# RF.net
KiCad netlist of a schematic drawn in Altium Designer
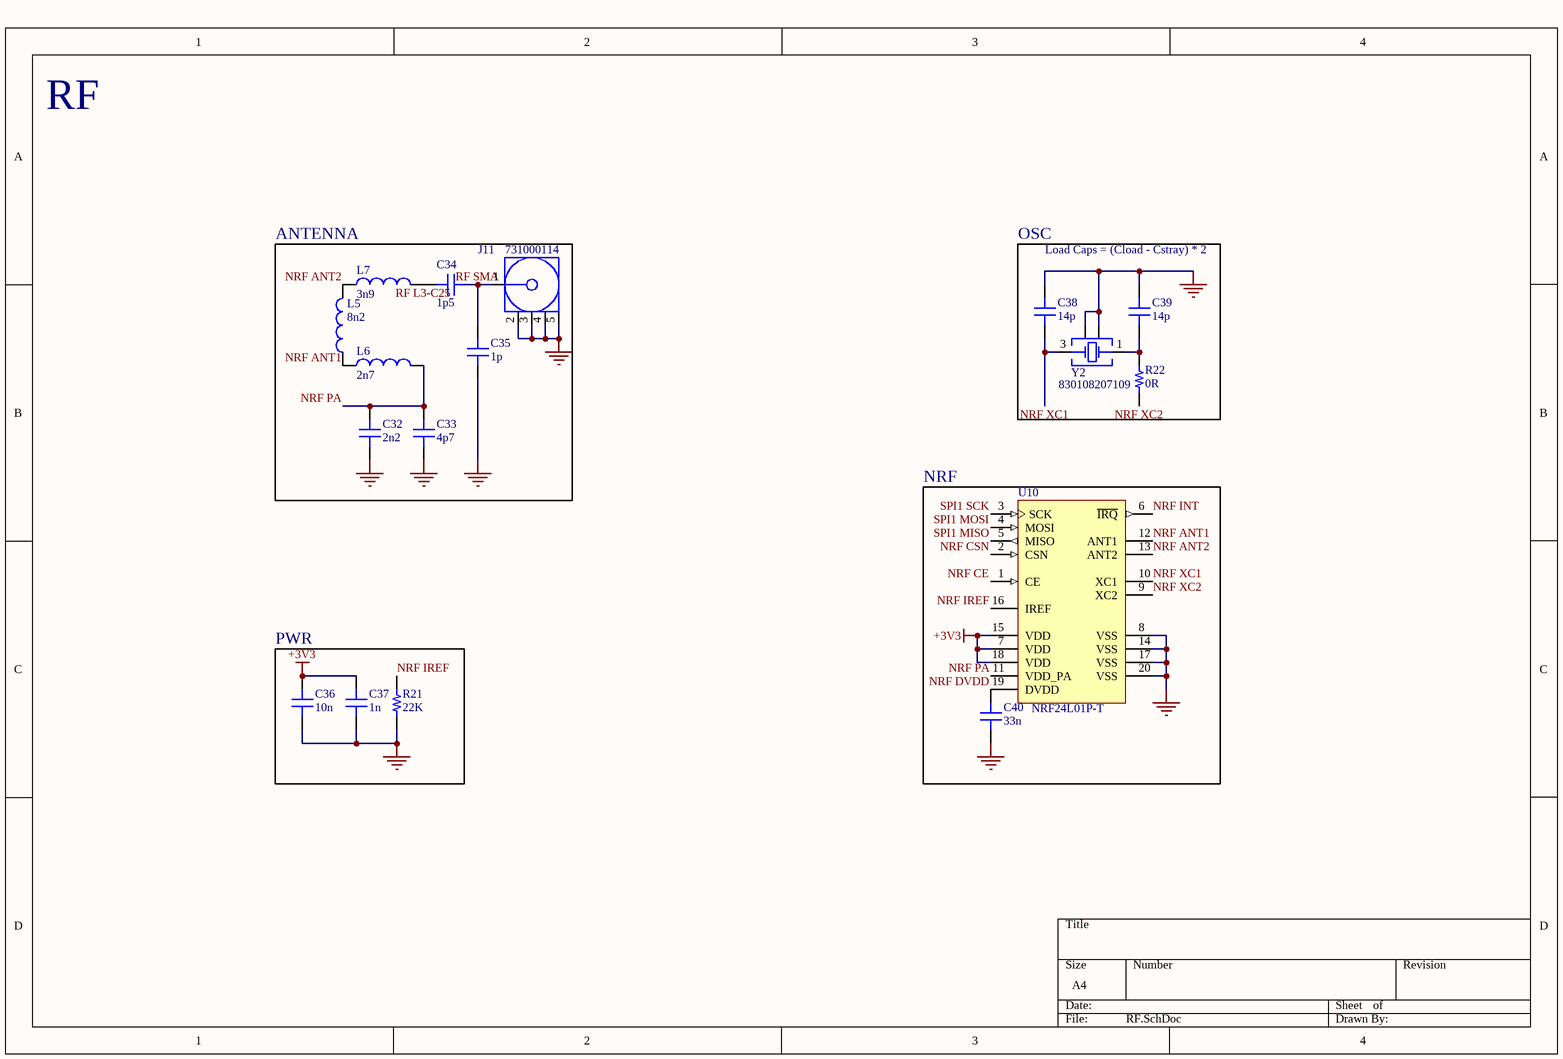
[diagram p0: RF.SchDoc]

(export (version "E")
  (design (tool "Eeschema 10.0.6"))
  (components
    (comp (ref "C32")
      (value "2n2")
      (footprint "CAP 0402_1005")
      (description "CAP CER 0402 10NF 16V X7R 10%")
      (fields (field (name "PART NUMBER") "C0402C103K4REC7867") (field (name "MANUFACTURER") "KEMET"))
      (libsource (lib "Celestial Altium Library - altium_library") (part "Capacitor"))
    )
    (comp (ref "C33")
      (value "4p7")
      (footprint "CAP 0402_1005")
      (description "CAP CER 0402 10NF 16V X7R 10%")
      (fields (field (name "PART NUMBER") "C0402C103K4REC7867") (field (name "MANUFACTURER") "KEMET"))
      (libsource (lib "Celestial Altium Library - altium_library") (part "Capacitor"))
    )
    (comp (ref "C34")
      (value "1p5")
      (footprint "CAP 0402_1005")
      (description "CAP CER 0402 10NF 16V X7R 10%")
      (fields (field (name "PART NUMBER") "C0402C103K4REC7867") (field (name "MANUFACTURER") "KEMET"))
      (libsource (lib "Celestial Altium Library - altium_library") (part "Capacitor"))
    )
    (comp (ref "C35")
      (value "1p")
      (footprint "CAP 0402_1005")
      (description "CAP CER 0402 10NF 16V X7R 10%")
      (fields (field (name "PART NUMBER") "C0402C103K4REC7867") (field (name "MANUFACTURER") "KEMET"))
      (libsource (lib "Celestial Altium Library - altium_library") (part "Capacitor"))
    )
    (comp (ref "C36")
      (value "10n")
      (footprint "CAP 0402_1005")
      (description "CAP CER 0402 10NF 16V X7R 10%")
      (fields (field (name "PART NUMBER") "C0402C103K4REC7867") (field (name "MANUFACTURER") "KEMET"))
      (libsource (lib "Celestial Altium Library - altium_library") (part "Capacitor"))
    )
    (comp (ref "C37")
      (value "1n")
      (footprint "CAP 0402_1005")
      (description "CAP CER 0402 10NF 16V X7R 10%")
      (fields (field (name "PART NUMBER") "C0402C103K4REC7867") (field (name "MANUFACTURER") "KEMET"))
      (libsource (lib "Celestial Altium Library - altium_library") (part "Capacitor"))
    )
    (comp (ref "C38")
      (value "14p")
      (footprint "CAP 0402_1005")
      (description "CAP CER 14PF 50V C0G/NP0 0402")
      (fields (field (name "PART NUMBER") "GJM1555C1H140GB01D"))
      (libsource (lib "Celestial Altium Library - altium_library") (part "Capacitor"))
    )
    (comp (ref "C39")
      (value "14p")
      (footprint "CAP 0402_1005")
      (description "CAP CER 14PF 50V C0G/NP0 0402")
      (fields (field (name "PART NUMBER") "GJM1555C1H140GB01D"))
      (libsource (lib "Celestial Altium Library - altium_library") (part "Capacitor"))
    )
    (comp (ref "C40")
      (value "33n")
      (footprint "CAP 0402_1005")
      (description "CAP CER 33PF 16V X7R 0402")
      (fields (field (name "PART NUMBER") "C0402C330J4RACAUTO") (field (name "MANUFACTURER") "KEMET"))
      (libsource (lib "Celestial Altium Library - altium_library") (part "Capacitor"))
    )
    (comp (ref "J11")
      (value "731000114")
      (footprint "MOLX-731000114_V")
      (description "SMA Right-Angle PCB Jack Receptacle, Brass Body, Gold Plated, 50 Ohm, 5-Pin THD, RoHS, Tray")
      (fields (field (name "MANUFACTURER") "Molex"))
      (libsource (lib "Altium Content Vault") (part "CN-S-4F-RF5"))
    )
    (comp (ref "L5")
      (value "8n2")
      (footprint "WE-TCI_0402")
      (description "744901039 Fixed Ind 3.9NH 340MA 500MOHM Sm")
      (libsource (lib "Altium Content Vault") (part "Inductor - 1"))
    )
    (comp (ref "L6")
      (value "2n7")
      (footprint "WE-TCI_0402")
      (description "744901039 Fixed Ind 3.9NH 340MA 500MOHM Sm")
      (libsource (lib "Altium Content Vault") (part "Inductor - 1"))
    )
    (comp (ref "L7")
      (value "3n9")
      (footprint "WE-TCI_0402")
      (description "744901039 Fixed Ind 3.9NH 340MA 500MOHM Sm")
      (libsource (lib "Altium Content Vault") (part "Inductor - 1"))
    )
    (comp (ref "R21")
      (value "22K")
      (footprint "RES 0402_1005")
      (description "RES 22.1K OHM 1% 1/16W 0402")
      (fields (field (name "PART NUMBER") "RC0402FR-0722K1L") (field (name "MANUFACTURER") "Yageo"))
      (libsource (lib "Celestial Altium Library - altium_library") (part "Resistor"))
    )
    (comp (ref "R22")
      (value "0R")
      (footprint "RES 0402_1005")
      (description "0402 JUMPER ON TAPE AND REEL")
      (fields (field (name "PART NUMBER") "5112"))
      (libsource (lib "Celestial Altium Library - altium_library") (part "Resistor"))
    )
    (comp (ref "U10")
      (value "NRF24L01P-T")
      (footprint "NRSC-QFN-20_L")
      (description "Single Chip Transceiver, 2.4 GHz, 60 mW, 1.9 to 3.6 V, -40 to 85 degC, 20-Pin QFN, RoHS, Tray")
      (fields (field (name "MANUFACTURER") "Nordic Semiconductor"))
      (libsource (lib "Altium Content Vault") (part "NRSC-NRF24L01P-QFN-20"))
    )
    (comp (ref "Y2")
      (value "830108207109")
      (footprint "WE-XTAL_CFPX-180")
      (description "830108207109 WE-XTAL Quartz Crystal")
      (libsource (lib "Altium Content Vault") (part "WE-XTAL_CFPX-180"))
    )
  )
  (nets
    (net (code "1") (name "+3V3") (class "Default")
      (node (ref "C36") (pin "2") (pinfunction "2_2") (pintype "passive"))
      (node (ref "C37") (pin "2") (pinfunction "2_2") (pintype "passive"))
      (node (ref "U10") (pin "15") (pinfunction "VDD_15") (pintype "power_in"))
      (node (ref "U10") (pin "18") (pinfunction "VDD_18") (pintype "power_in"))
      (node (ref "U10") (pin "7") (pinfunction "VDD_7") (pintype "power_in"))
    )
    (net (code "2") (name "/NRF ANT1") (class "Default")
      (node (ref "L5") (pin "1") (pinfunction "1_1") (pintype "passive"))
      (node (ref "L6") (pin "1") (pinfunction "1_1") (pintype "passive"))
      (node (ref "U10") (pin "12") (pinfunction "ANT1_12") (pintype "passive"))
    )
    (net (code "3") (name "/NRF ANT2") (class "Default")
      (node (ref "L5") (pin "2") (pinfunction "2_2") (pintype "passive"))
      (node (ref "L7") (pin "1") (pinfunction "1_1") (pintype "passive"))
      (node (ref "U10") (pin "13") (pinfunction "ANT2_13") (pintype "passive"))
    )
    (net (code "4") (name "/NRF CE") (class "Default")
      (node (ref "U10") (pin "1") (pinfunction "CE_1") (pintype "input"))
    )
    (net (code "5") (name "/NRF CSN") (class "Default")
      (node (ref "U10") (pin "2") (pinfunction "CSN_2") (pintype "input"))
    )
    (net (code "6") (name "/NRF DVDD") (class "Default")
      (node (ref "C40") (pin "2") (pinfunction "2_2") (pintype "passive"))
      (node (ref "U10") (pin "19") (pinfunction "DVDD_19") (pintype "power_in"))
    )
    (net (code "7") (name "/NRF INT") (class "Default")
      (node (ref "U10") (pin "6") (pinfunction "~{IRQ}_6") (pintype "output"))
    )
    (net (code "8") (name "/NRF IREF") (class "Default")
      (node (ref "R21") (pin "1") (pinfunction "1_1") (pintype "passive"))
      (node (ref "U10") (pin "16") (pinfunction "IREF_16") (pintype "passive"))
    )
    (net (code "9") (name "/NRF PA") (class "Default")
      (node (ref "C32") (pin "2") (pinfunction "2_2") (pintype "passive"))
      (node (ref "C33") (pin "2") (pinfunction "2_2") (pintype "passive"))
      (node (ref "L6") (pin "2") (pinfunction "2_2") (pintype "passive"))
      (node (ref "U10") (pin "11") (pinfunction "VDD_PA_11") (pintype "power_in"))
    )
    (net (code "10") (name "/NRF XC1") (class "Default")
      (node (ref "C38") (pin "1") (pinfunction "1_1") (pintype "passive"))
      (node (ref "U10") (pin "10") (pinfunction "XC1_10") (pintype "passive"))
      (node (ref "Y2") (pin "3") (pinfunction "Crystal_3") (pintype "passive"))
    )
    (net (code "11") (name "/NRF XC2") (class "Default")
      (node (ref "R22") (pin "2") (pinfunction "2_2") (pintype "passive"))
      (node (ref "U10") (pin "9") (pinfunction "XC2_9") (pintype "passive"))
    )
    (net (code "12") (name "/RF L3-C25") (class "Default")
      (node (ref "C34") (pin "2") (pinfunction "2_2") (pintype "passive"))
      (node (ref "L7") (pin "2") (pinfunction "2_2") (pintype "passive"))
    )
    (net (code "13") (name "/RF SMA") (class "Default")
      (node (ref "C34") (pin "1") (pinfunction "1_1") (pintype "passive"))
      (node (ref "C35") (pin "2") (pinfunction "2_2") (pintype "passive"))
      (node (ref "J11") (pin "1") (pinfunction "1_1") (pintype "passive"))
    )
    (net (code "14") (name "/SPI1 MISO") (class "Default")
      (node (ref "U10") (pin "5") (pinfunction "MISO_5") (pintype "output"))
    )
    (net (code "15") (name "/SPI1 MOSI") (class "Default")
      (node (ref "U10") (pin "4") (pinfunction "MOSI_4") (pintype "input"))
    )
    (net (code "16") (name "/SPI1 SCK") (class "Default")
      (node (ref "U10") (pin "3") (pinfunction "SCK_3") (pintype "input"))
    )
    (net (code "17") (name "GND") (class "Default")
      (node (ref "C32") (pin "1") (pinfunction "1_1") (pintype "passive"))
      (node (ref "C33") (pin "1") (pinfunction "1_1") (pintype "passive"))
      (node (ref "C35") (pin "1") (pinfunction "1_1") (pintype "passive"))
      (node (ref "C36") (pin "1") (pinfunction "1_1") (pintype "passive"))
      (node (ref "C37") (pin "1") (pinfunction "1_1") (pintype "passive"))
      (node (ref "C38") (pin "2") (pinfunction "2_2") (pintype "passive"))
      (node (ref "C39") (pin "2") (pinfunction "2_2") (pintype "passive"))
      (node (ref "C40") (pin "1") (pinfunction "1_1") (pintype "passive"))
      (node (ref "J11") (pin "2") (pinfunction "2_2") (pintype "passive"))
      (node (ref "J11") (pin "3") (pinfunction "3_3") (pintype "passive"))
      (node (ref "J11") (pin "4") (pinfunction "4_4") (pintype "passive"))
      (node (ref "J11") (pin "5") (pinfunction "5_5") (pintype "passive"))
      (node (ref "R21") (pin "2") (pinfunction "2_2") (pintype "passive"))
      (node (ref "U10") (pin "14") (pinfunction "VSS_14") (pintype "power_in"))
      (node (ref "U10") (pin "17") (pinfunction "VSS_17") (pintype "power_in"))
      (node (ref "U10") (pin "20") (pinfunction "VSS_20") (pintype "power_in"))
      (node (ref "U10") (pin "8") (pinfunction "VSS_8") (pintype "power_in"))
      (node (ref "Y2") (pin "2") (pinfunction "GND&Lid_2") (pintype "passive"))
      (node (ref "Y2") (pin "4") (pinfunction "GND&Lid_4") (pintype "passive"))
    )
    (net (code "18") (name "Net-(C39-Pad1)") (class "Default")
      (node (ref "C39") (pin "1") (pinfunction "1_1") (pintype "passive"))
      (node (ref "R22") (pin "1") (pinfunction "1_1") (pintype "passive"))
      (node (ref "Y2") (pin "1") (pinfunction "Crystal_1") (pintype "passive"))
    )
  )
)
